# aedr_breakout.net
KiCad netlist of a schematic drawn in EAGLE
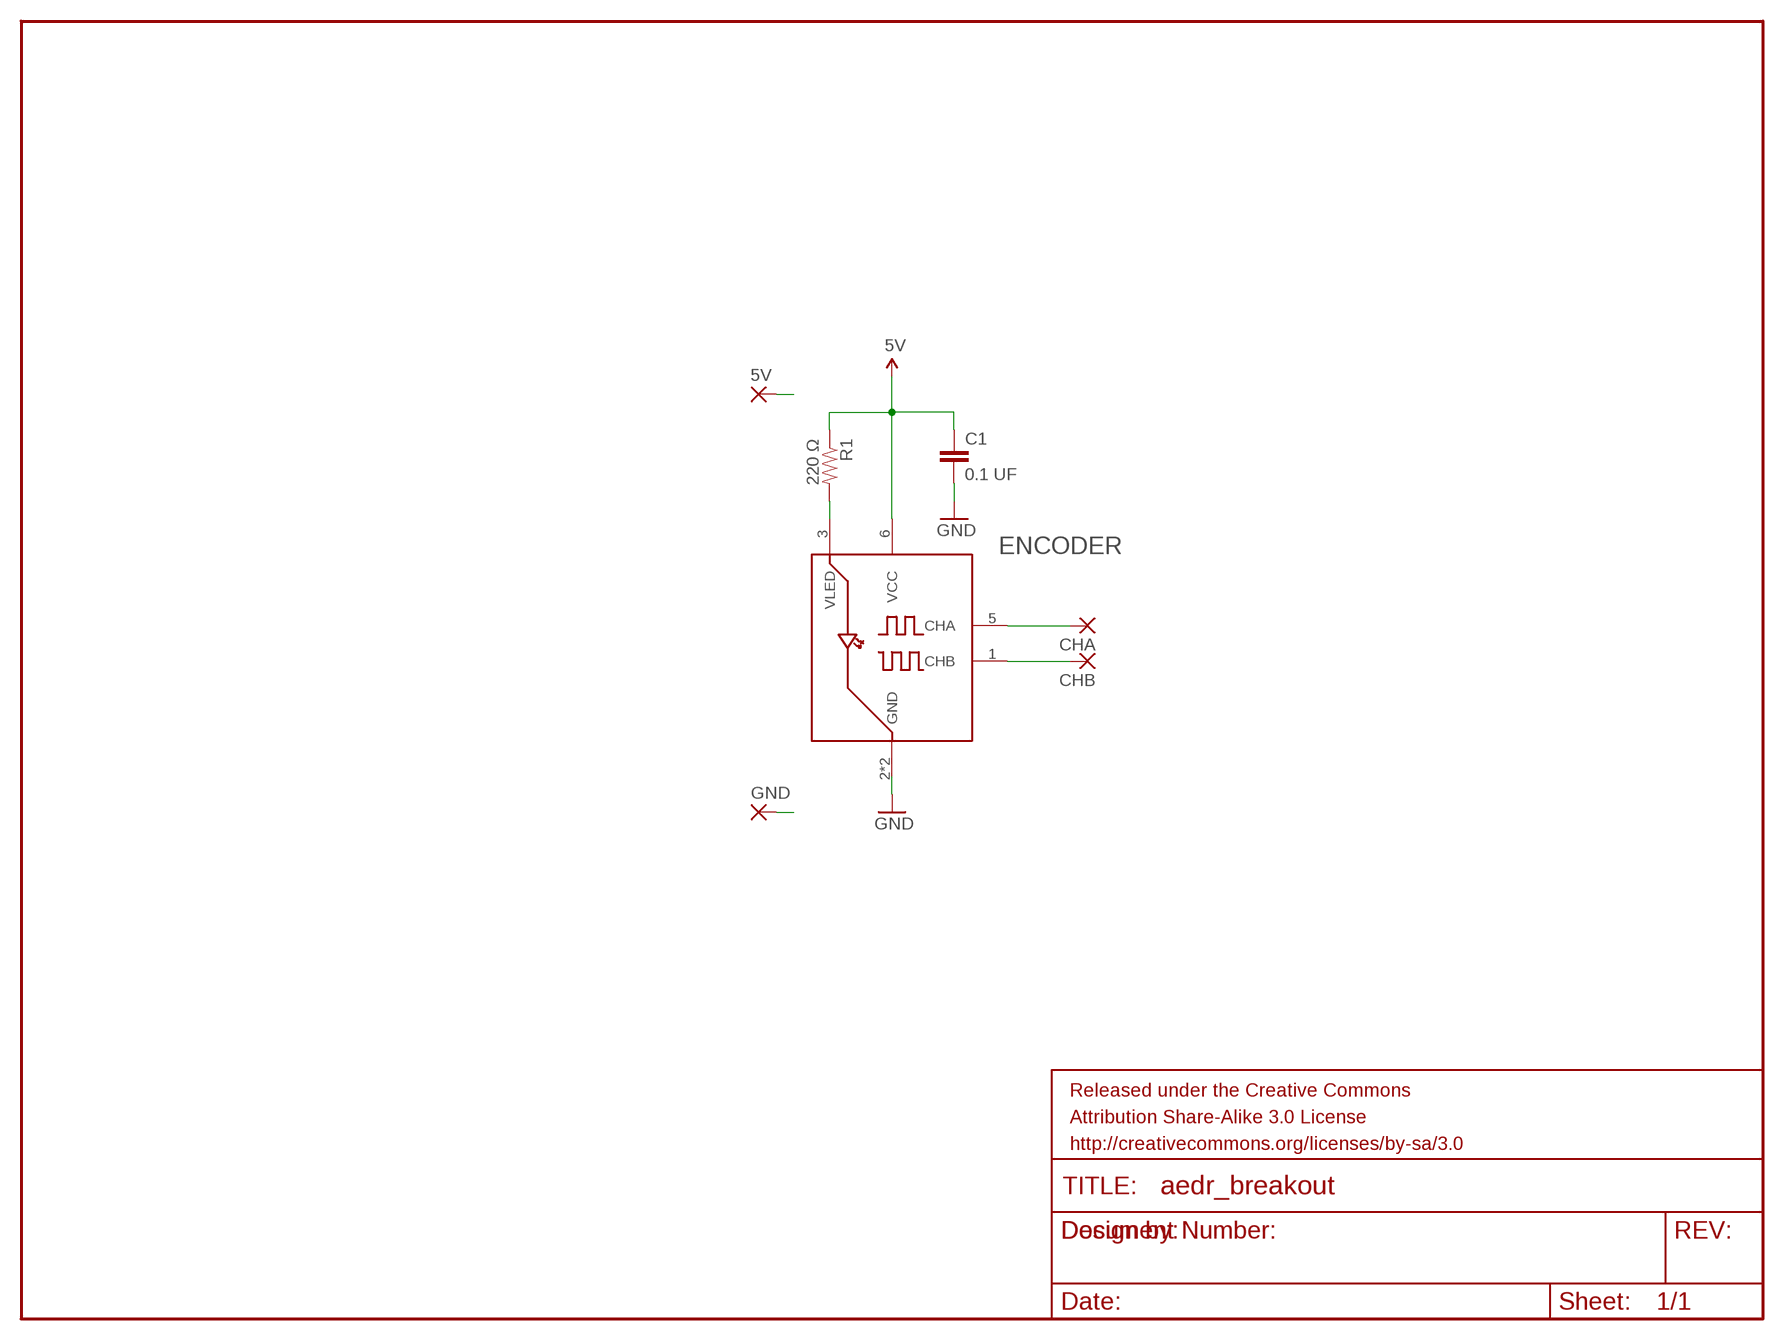
[diagram p0: schematic, sheet 1]

(export (version "E")
  (design (tool "Eeschema 10.0.6"))
  (components
    (comp (ref "5V")
      (value "WIREPADSMD1,27-254")
      (footprint "eagle-import:SMD1,27-2,54")
      (libsource (lib "eagle-import") (part "WIREPADSMD1,27-254"))
    )
    (comp (ref "C1")
      (value "0.1 UF")
      (footprint "eagle-import:0402-CAP")
      (libsource (lib "eagle-import") (part "CAP0402-CAP"))
    )
    (comp (ref "CHA")
      (value "WIREPADSMD1,27-254")
      (footprint "eagle-import:SMD1,27-2,54")
      (libsource (lib "eagle-import") (part "WIREPADSMD1,27-254"))
    )
    (comp (ref "CHB")
      (value "WIREPADSMD1,27-254")
      (footprint "eagle-import:SMD1,27-2,54")
      (libsource (lib "eagle-import") (part "WIREPADSMD1,27-254"))
    )
    (comp (ref "ENCODER")
      (value "AEDR-8300-K")
      (footprint "eagle-import:AEDR-8300")
      (libsource (lib "eagle-import") (part "AEDR-8300-K"))
    )
    (comp (ref "GND")
      (value "WIREPADSMD1,27-254")
      (footprint "eagle-import:SMD1,27-2,54")
      (libsource (lib "eagle-import") (part "WIREPADSMD1,27-254"))
    )
    (comp (ref "R1")
      (value "220 Ω")
      (footprint "eagle-import:0402-RES")
      (libsource (lib "eagle-import") (part "RESISTOR0402-RES"))
    )
  )
  (nets
    (net (code "1") (name "5V") (class "Default")
      (node (ref "5V") (pin "1") (pinfunction "P_1") (pintype "passive"))
      (node (ref "C1") (pin "1") (pinfunction "1_1") (pintype "passive"))
      (node (ref "ENCODER") (pin "6") (pinfunction "VCC_6") (pintype "bidirectional"))
      (node (ref "R1") (pin "1") (pinfunction "1_1") (pintype "passive"))
    )
    (net (code "2") (name "GND") (class "Default")
      (node (ref "C1") (pin "2") (pinfunction "2_2") (pintype "passive"))
      (node (ref "ENCODER") (pin "2") (pinfunction "GND_2") (pintype "bidirectional"))
      (node (ref "ENCODER") (pin "4") (pinfunction "GND_4") (pintype "bidirectional"))
    )
    (net (code "3") (name "Net-(CHA-P)") (class "Default")
      (node (ref "CHA") (pin "1") (pinfunction "P_1") (pintype "passive"))
      (node (ref "ENCODER") (pin "5") (pinfunction "CHA_5") (pintype "bidirectional"))
    )
    (net (code "4") (name "Net-(CHB-P)") (class "Default")
      (node (ref "CHB") (pin "1") (pinfunction "P_1") (pintype "passive"))
      (node (ref "ENCODER") (pin "1") (pinfunction "CHB_1") (pintype "bidirectional"))
    )
    (net (code "5") (name "Net-(ENCODER-VLED)") (class "Default")
      (node (ref "ENCODER") (pin "3") (pinfunction "VLED_3") (pintype "bidirectional"))
      (node (ref "R1") (pin "2") (pinfunction "2_2") (pintype "passive"))
    )
    (net (code "6") (name "unconnected-(GND-P-Pad1)") (class "Default")
      (node (ref "GND") (pin "1") (pinfunction "P_1") (pintype "passive"))
    )
  )
)
